# Radio.net
KiCad netlist of a schematic drawn in Altium Designer
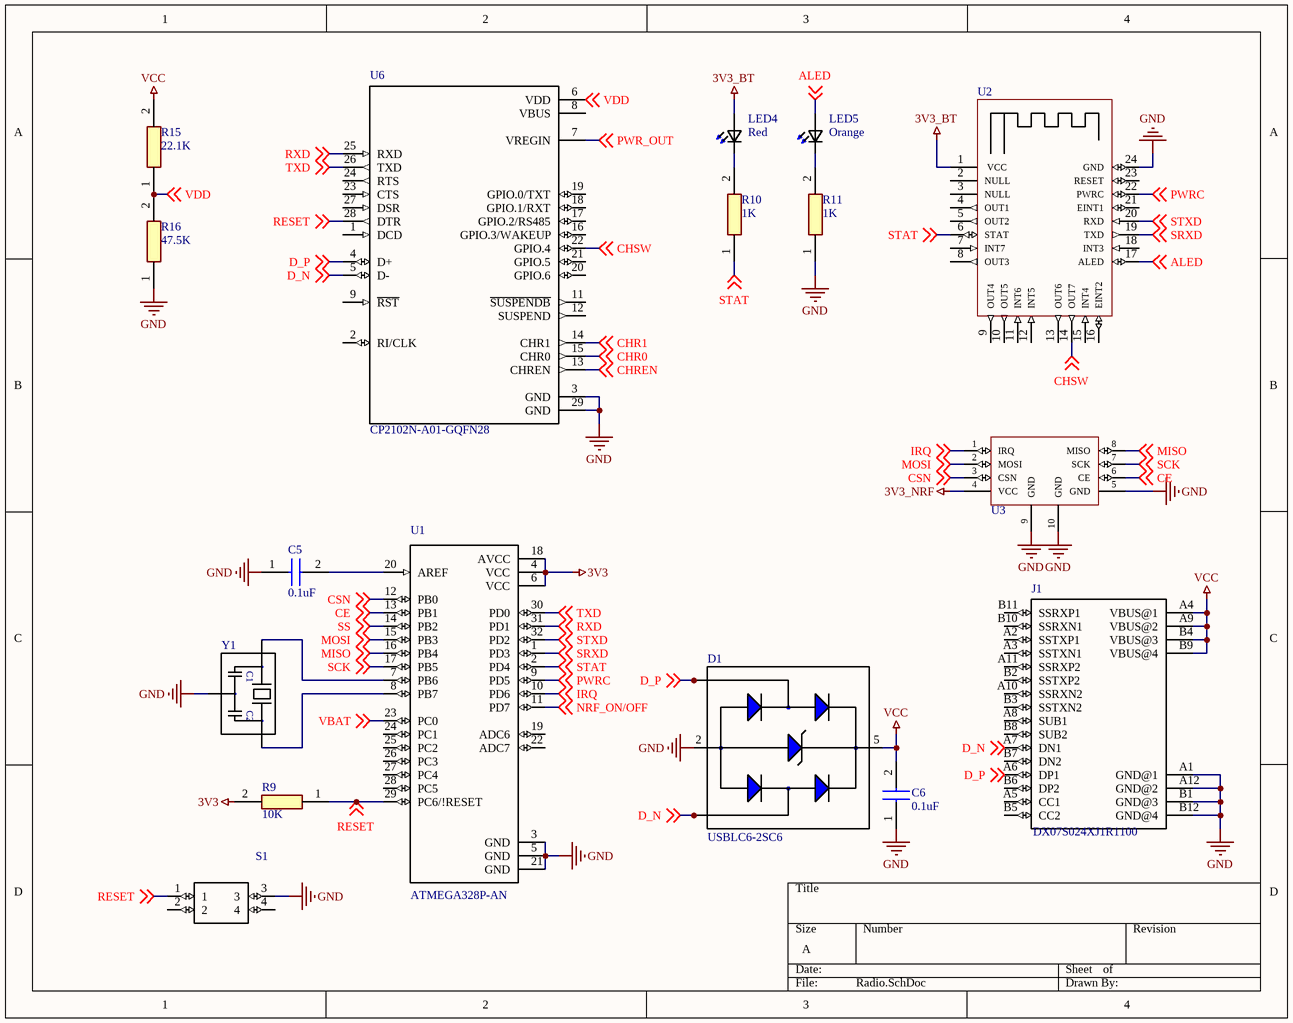
[diagram p0: Radio.SchDoc]

(export (version "E")
  (design (tool "Eeschema 10.0.6"))
  (components
    (comp (ref "C5")
      (value "0.1uF")
      (footprint "*CAPC1608X95N")
      (description "Capacitor")
      (fields (field (name "Comment") "capacitor 0603"))
      (libsource (lib "Radio Lib") (part "capacitor 0603"))
    )
    (comp (ref "C6")
      (value "0.1uF")
      (footprint "*CAPC1608X95N")
      (description "Capacitor")
      (fields (field (name "Comment") "capacitor 0603"))
      (libsource (lib "Radio Lib") (part "capacitor 0603"))
    )
    (comp (ref "D1")
      (value "USBLC6-2SC6")
      (footprint "*SOT95P280X145-6N")
      (description "USBLC6 Series 2 Line 6 V Uni / Bi-Directional ESD Protection - SOT-23-6")
      (fields (field (name "MF") "STMicroelectronics"))
      (libsource (lib "Radio Lib") (part "USBLC6-2SC6"))
    )
    (comp (ref "J1")
      (value "DX07S024XJ1R1100")
      (footprint "*JAE_DX07S024XJ1R1100_DX07S024XJ1R1100(Primary)")
      (description "Cut Tape - Usb Type c Receptacle Mid Mnt Dual r")
      (fields (field (name "MF") "JAE Electronics"))
      (libsource (lib "Radio Lib") (part "DX07S024XJ1R1100"))
    )
    (comp (ref "LED4")
      (value "Red")
      (footprint "*0603")
      (description "LED Indication - Discrete 3.4V 0603 _1608 Metric_")
      (fields (field (name "MP") "HSMR-C191") (field (name "MF") "Broadcom Limited"))
      (libsource (lib "Radio Lib") (part "HSMR-C191"))
    )
    (comp (ref "LED5")
      (value "Orange")
      (footprint "*0603")
      (description "LED Indication - Discrete 3.4V 0603 _1608 Metric_")
      (fields (field (name "MP") "HSMR-C191") (field (name "MF") "Broadcom Limited"))
      (libsource (lib "Radio Lib") (part "HSMR-C191"))
    )
    (comp (ref "R9")
      (value "10K")
      (footprint "RESC1608X55N")
      (description "Resistor")
      (fields (field (name "Comment") "resistor"))
      (libsource (lib "") (part "resistor_1"))
    )
    (comp (ref "R10")
      (value "1K")
      (footprint "RESC1608X55N")
      (description "Resistor")
      (fields (field (name "Comment") "resistor"))
      (libsource (lib "Radio Lib") (part "resistor"))
    )
    (comp (ref "R11")
      (value "1K")
      (footprint "RESC1608X55N")
      (description "Resistor")
      (fields (field (name "Comment") "resistor"))
      (libsource (lib "Radio Lib") (part "resistor"))
    )
    (comp (ref "R15")
      (value "22.1K")
      (footprint "RESC1608X55N")
      (description "Resistor")
      (fields (field (name "Comment") "resistor"))
      (libsource (lib "Radio Lib") (part "resistor"))
    )
    (comp (ref "R16")
      (value "47.5K")
      (footprint "RESC1608X55N")
      (description "Resistor")
      (fields (field (name "Comment") "resistor"))
      (libsource (lib "Radio Lib") (part "resistor"))
    )
    (comp (ref "S1")
      (value "PTS810SJK250SMTRLFS")
      (footprint "*PTS810SJG250SMTRLFS")
      (description "Tactile Switch SPST-NO Top Actuated Surface Mount")
      (fields (field (name "MP") "PTS810 SJK 250 SMTR LFS") (field (name "MF") "C&K"))
      (libsource (lib "Radio Lib") (part "PTS810SJK250SMTRLFS"))
    )
    (comp (ref "U1")
      (value "ATMEGA328P-AN")
      (footprint "*QFP80P900X900X120-32N")
      (description "AVR AVRÂ® ATmega Microcontroller IC 8-Bit 20MHz 32KB _16K x 16_ FLASH 32-TQFP _7x7_")
      (fields (field (name "MF") "Microchip"))
      (libsource (lib "Radio Lib") (part "ATMEGA328P-AN"))
    )
    (comp (ref "U2")
      (value "JDY-23")
      (footprint "*JDY-23")
      (description "Bluetooth Bluetooth v4.0 Transceiver Module 2.4GHz Integrated, Chip Surface Mount")
      (fields (field (name "MF") "Sierra Wireless"))
      (libsource (lib "Radio Lib") (part "JDY-23"))
    )
    (comp (ref "U3")
      (value "NRF24L01P+")
      (footprint "NRF24L01P+")
      (libsource (lib "Radio Lib") (part "NRF24L01P+"))
    )
    (comp (ref "U6")
      (value "CP2102N-A01-GQFN28")
      (footprint "*QFN50P500X500X80-29N")
      (description "USB Bridge, USB to UART USB 2.0 UART Interface 28-QFN _5x5_")
      (fields (field (name "MF") "Silicon Labs"))
      (libsource (lib "Radio Lib") (part "CP2102N-A01-GQFN28"))
    )
    (comp (ref "Y1")
      (value "PBRC8.00MR10X000")
      (footprint "*XTAL_PBRC8.00MR10X000")
      (description "8MHz Ceramic Resonator Built in Capacitor 15pF Â±0.1% -40Â°C ~ 85Â°C Surface Mount")
      (fields (field (name "MF") "Kyocera International"))
      (libsource (lib "Radio Lib") (part "PBRC8.00MR10X000"))
    )
  )
  (nets
    (net (code "1") (name "3V3") (class "Default")
      (node (ref "R9") (pin "2") (pinfunction "2_2") (pintype "passive"))
      (node (ref "U1") (pin "18") (pinfunction "AVCC_18") (pintype "power_in"))
      (node (ref "U1") (pin "4") (pinfunction "VCC_4") (pintype "power_in"))
      (node (ref "U1") (pin "6") (pinfunction "VCC_6") (pintype "power_in"))
    )
    (net (code "2") (name "3V3_BT") (class "Default")
      (node (ref "LED4") (pin "2") (pinfunction "A2_2") (pintype "passive"))
      (node (ref "U2") (pin "1") (pinfunction "VCC_1") (pintype "power_in"))
    )
    (net (code "3") (name "3V3_NRF") (class "Default")
      (node (ref "U3") (pin "4") (pinfunction "VCC_4") (pintype "power_in"))
    )
    (net (code "4") (name "ALED") (class "Default")
      (node (ref "LED5") (pin "2") (pinfunction "A2_2") (pintype "passive"))
      (node (ref "U2") (pin "17") (pinfunction "ALED_17") (pintype "bidirectional"))
    )
    (net (code "5") (name "CE") (class "Default")
      (node (ref "U1") (pin "13") (pinfunction "PB1_13") (pintype "bidirectional"))
      (node (ref "U3") (pin "6") (pinfunction "CE_6") (pintype "bidirectional"))
    )
    (net (code "6") (name "CHR0") (class "Default")
      (node (ref "U6") (pin "15") (pinfunction "CHR0_15") (pintype "output"))
    )
    (net (code "7") (name "CHR1") (class "Default")
      (node (ref "U6") (pin "14") (pinfunction "CHR1_14") (pintype "output"))
    )
    (net (code "8") (name "CHREN") (class "Default")
      (node (ref "U6") (pin "13") (pinfunction "CHREN_13") (pintype "output"))
    )
    (net (code "9") (name "CHSW") (class "Default")
      (node (ref "U2") (pin "14") (pinfunction "OUT7_14") (pintype "output"))
      (node (ref "U6") (pin "22") (pinfunction "GPIO.4_22") (pintype "bidirectional"))
    )
    (net (code "10") (name "CSN") (class "Default")
      (node (ref "U1") (pin "12") (pinfunction "PB0_12") (pintype "bidirectional"))
      (node (ref "U3") (pin "3") (pinfunction "CSN_3") (pintype "bidirectional"))
    )
    (net (code "11") (name "D_N") (class "Default")
      (node (ref "D1") (pin "3") (pinfunction "I/O2_3") (pintype "bidirectional"))
      (node (ref "D1") (pin "4") (pinfunction "I/O2_4") (pintype "bidirectional"))
      (node (ref "J1") (pin "A7") (pinfunction "DN1_A7") (pintype "bidirectional"))
      (node (ref "U6") (pin "5") (pinfunction "D-_5") (pintype "bidirectional"))
    )
    (net (code "12") (name "D_P") (class "Default")
      (node (ref "D1") (pin "1") (pinfunction "I/O1_1") (pintype "bidirectional"))
      (node (ref "D1") (pin "6") (pinfunction "I/O1_6") (pintype "bidirectional"))
      (node (ref "J1") (pin "A6") (pinfunction "DP1_A6") (pintype "bidirectional"))
      (node (ref "U6") (pin "4") (pinfunction "D+_4") (pintype "bidirectional"))
    )
    (net (code "13") (name "GND") (class "Default")
      (node (ref "C5") (pin "1") (pinfunction "1_1") (pintype "passive"))
      (node (ref "C6") (pin "1") (pinfunction "1_1") (pintype "passive"))
      (node (ref "D1") (pin "2") (pinfunction "GND_2") (pintype "power_in"))
      (node (ref "J1") (pin "A1") (pinfunction "GND@1_A1") (pintype "power_in"))
      (node (ref "J1") (pin "A12") (pinfunction "GND@2_A12") (pintype "power_in"))
      (node (ref "J1") (pin "B1") (pinfunction "GND@3_B1") (pintype "power_in"))
      (node (ref "J1") (pin "B12") (pinfunction "GND@4_B12") (pintype "power_in"))
      (node (ref "R11") (pin "1") (pinfunction "1_1") (pintype "passive"))
      (node (ref "R16") (pin "1") (pinfunction "1_1") (pintype "passive"))
      (node (ref "S1") (pin "3") (pinfunction "3_3") (pintype "bidirectional"))
      (node (ref "U1") (pin "21") (pinfunction "GND_21") (pintype "power_in"))
      (node (ref "U1") (pin "3") (pinfunction "GND_3") (pintype "power_in"))
      (node (ref "U1") (pin "5") (pinfunction "GND_5") (pintype "power_in"))
      (node (ref "U2") (pin "24") (pinfunction "GND_24") (pintype "bidirectional"))
      (node (ref "U3") (pin "10") (pinfunction "GND_10") (pintype "power_in"))
      (node (ref "U3") (pin "5") (pinfunction "GND_5") (pintype "power_in"))
      (node (ref "U3") (pin "9") (pinfunction "GND_9") (pintype "power_in"))
      (node (ref "U6") (pin "29") (pinfunction "GND_29") (pintype "power_in"))
      (node (ref "U6") (pin "3") (pinfunction "GND_3") (pintype "power_in"))
      (node (ref "Y1") (pin "2") (pinfunction "GND_2") (pintype "passive"))
    )
    (net (code "14") (name "IRQ") (class "Default")
      (node (ref "U1") (pin "10") (pinfunction "PD6_10") (pintype "bidirectional"))
      (node (ref "U3") (pin "1") (pinfunction "IRQ_1") (pintype "bidirectional"))
    )
    (net (code "15") (name "MISO") (class "Default")
      (node (ref "U1") (pin "16") (pinfunction "PB4_16") (pintype "bidirectional"))
      (node (ref "U3") (pin "8") (pinfunction "MISO_8") (pintype "bidirectional"))
    )
    (net (code "16") (name "MOSI") (class "Default")
      (node (ref "U1") (pin "15") (pinfunction "PB3_15") (pintype "bidirectional"))
      (node (ref "U3") (pin "2") (pinfunction "MOSI_2") (pintype "bidirectional"))
    )
    (net (code "17") (name "NRF_ON{slash}OFF") (class "Default")
      (node (ref "U1") (pin "11") (pinfunction "PD7_11") (pintype "bidirectional"))
    )
    (net (code "18") (name "Net-(LED4-K2)") (class "Default")
      (node (ref "LED4") (pin "1") (pinfunction "K2_1") (pintype "passive"))
      (node (ref "R10") (pin "2") (pinfunction "2_2") (pintype "passive"))
    )
    (net (code "19") (name "Net-(LED5-K2)") (class "Default")
      (node (ref "LED5") (pin "1") (pinfunction "K2_1") (pintype "passive"))
      (node (ref "R11") (pin "2") (pinfunction "2_2") (pintype "passive"))
    )
    (net (code "20") (name "Net-(U1-AREF)") (class "Default")
      (node (ref "C5") (pin "2") (pinfunction "2_2") (pintype "passive"))
      (node (ref "U1") (pin "20") (pinfunction "AREF_20") (pintype "input"))
    )
    (net (code "21") (name "Net-(U1-PB6)") (class "Default")
      (node (ref "U1") (pin "7") (pinfunction "PB6_7") (pintype "bidirectional"))
      (node (ref "Y1") (pin "1") (pinfunction "IN_1") (pintype "passive"))
    )
    (net (code "22") (name "Net-(U1-PB7)") (class "Default")
      (node (ref "U1") (pin "8") (pinfunction "PB7_8") (pintype "bidirectional"))
      (node (ref "Y1") (pin "3") (pinfunction "OUT_3") (pintype "passive"))
    )
    (net (code "23") (name "PWRC") (class "Default")
      (node (ref "U1") (pin "9") (pinfunction "PD5_9") (pintype "bidirectional"))
      (node (ref "U2") (pin "22") (pinfunction "PWRC_22") (pintype "bidirectional"))
    )
    (net (code "24") (name "PWR_OUT") (class "Default")
      (node (ref "U6") (pin "7") (pinfunction "VREGIN_7") (pintype "power_in"))
    )
    (net (code "25") (name "RESET") (class "Default")
      (node (ref "R9") (pin "1") (pinfunction "1_1") (pintype "passive"))
      (node (ref "S1") (pin "1") (pinfunction "1_1") (pintype "bidirectional"))
      (node (ref "U1") (pin "29") (pinfunction "PC6/!RESET_29") (pintype "bidirectional"))
      (node (ref "U6") (pin "28") (pinfunction "DTR_28") (pintype "output"))
    )
    (net (code "26") (name "RXD") (class "Default")
      (node (ref "U1") (pin "31") (pinfunction "PD1_31") (pintype "bidirectional"))
      (node (ref "U6") (pin "25") (pinfunction "RXD_25") (pintype "input"))
    )
    (net (code "27") (name "SCK") (class "Default")
      (node (ref "U1") (pin "17") (pinfunction "PB5_17") (pintype "bidirectional"))
      (node (ref "U3") (pin "7") (pinfunction "SCK_7") (pintype "bidirectional"))
    )
    (net (code "28") (name "SRXD") (class "Default")
      (node (ref "U1") (pin "1") (pinfunction "PD3_1") (pintype "bidirectional"))
      (node (ref "U2") (pin "19") (pinfunction "TXD_19") (pintype "output"))
    )
    (net (code "29") (name "SS") (class "Default")
      (node (ref "U1") (pin "14") (pinfunction "PB2_14") (pintype "bidirectional"))
    )
    (net (code "30") (name "STAT") (class "Default")
      (node (ref "R10") (pin "1") (pinfunction "1_1") (pintype "passive"))
      (node (ref "U1") (pin "2") (pinfunction "PD4_2") (pintype "bidirectional"))
      (node (ref "U2") (pin "6") (pinfunction "STAT_6") (pintype "bidirectional"))
    )
    (net (code "31") (name "STXD") (class "Default")
      (node (ref "U1") (pin "32") (pinfunction "PD2_32") (pintype "bidirectional"))
      (node (ref "U2") (pin "20") (pinfunction "RXD_20") (pintype "input"))
    )
    (net (code "32") (name "TXD") (class "Default")
      (node (ref "U1") (pin "30") (pinfunction "PD0_30") (pintype "bidirectional"))
      (node (ref "U6") (pin "26") (pinfunction "TXD_26") (pintype "output"))
    )
    (net (code "33") (name "VBAT") (class "Default")
      (node (ref "U1") (pin "23") (pinfunction "PC0_23") (pintype "bidirectional"))
    )
    (net (code "34") (name "VCC") (class "Default")
      (node (ref "C6") (pin "2") (pinfunction "2_2") (pintype "passive"))
      (node (ref "D1") (pin "5") (pinfunction "VBUS_5") (pintype "power_in"))
      (node (ref "J1") (pin "A4") (pinfunction "VBUS@1_A4") (pintype "power_in"))
      (node (ref "J1") (pin "A9") (pinfunction "VBUS@2_A9") (pintype "power_in"))
      (node (ref "J1") (pin "B4") (pinfunction "VBUS@3_B4") (pintype "power_in"))
      (node (ref "J1") (pin "B9") (pinfunction "VBUS@4_B9") (pintype "power_in"))
      (node (ref "R15") (pin "2") (pinfunction "2_2") (pintype "passive"))
    )
    (net (code "35") (name "VDD") (class "Default")
      (node (ref "R15") (pin "1") (pinfunction "1_1") (pintype "passive"))
      (node (ref "R16") (pin "2") (pinfunction "2_2") (pintype "passive"))
      (node (ref "U6") (pin "6") (pinfunction "VDD_6") (pintype "power_in"))
    )
    (net (code "36") (name "unconnected-(J1-CC1-PadA5)") (class "Default")
      (node (ref "J1") (pin "A5") (pinfunction "CC1_A5") (pintype "bidirectional"))
    )
    (net (code "37") (name "unconnected-(J1-CC2-PadB5)") (class "Default")
      (node (ref "J1") (pin "B5") (pinfunction "CC2_B5") (pintype "bidirectional"))
    )
    (net (code "38") (name "unconnected-(J1-DN2-PadB7)") (class "Default")
      (node (ref "J1") (pin "B7") (pinfunction "DN2_B7") (pintype "bidirectional"))
    )
    (net (code "39") (name "unconnected-(J1-DP2-PadB6)") (class "Default")
      (node (ref "J1") (pin "B6") (pinfunction "DP2_B6") (pintype "bidirectional"))
    )
    (net (code "40") (name "unconnected-(J1-SSRXN1-PadB10)") (class "Default")
      (node (ref "J1") (pin "B10") (pinfunction "SSRXN1_B10") (pintype "bidirectional"))
    )
    (net (code "41") (name "unconnected-(J1-SSRXN2-PadA10)") (class "Default")
      (node (ref "J1") (pin "A10") (pinfunction "SSRXN2_A10") (pintype "bidirectional"))
    )
    (net (code "42") (name "unconnected-(J1-SSRXP1-PadB11)") (class "Default")
      (node (ref "J1") (pin "B11") (pinfunction "SSRXP1_B11") (pintype "bidirectional"))
    )
    (net (code "43") (name "unconnected-(J1-SSRXP2-PadA11)") (class "Default")
      (node (ref "J1") (pin "A11") (pinfunction "SSRXP2_A11") (pintype "bidirectional"))
    )
    (net (code "44") (name "unconnected-(J1-SSTXN1-PadA3)") (class "Default")
      (node (ref "J1") (pin "A3") (pinfunction "SSTXN1_A3") (pintype "bidirectional"))
    )
    (net (code "45") (name "unconnected-(J1-SSTXN2-PadB3)") (class "Default")
      (node (ref "J1") (pin "B3") (pinfunction "SSTXN2_B3") (pintype "bidirectional"))
    )
    (net (code "46") (name "unconnected-(J1-SSTXP1-PadA2)") (class "Default")
      (node (ref "J1") (pin "A2") (pinfunction "SSTXP1_A2") (pintype "bidirectional"))
    )
    (net (code "47") (name "unconnected-(J1-SSTXP2-PadB2)") (class "Default")
      (node (ref "J1") (pin "B2") (pinfunction "SSTXP2_B2") (pintype "bidirectional"))
    )
    (net (code "48") (name "unconnected-(J1-SUB1-PadA8)") (class "Default")
      (node (ref "J1") (pin "A8") (pinfunction "SUB1_A8") (pintype "bidirectional"))
    )
    (net (code "49") (name "unconnected-(J1-SUB2-PadB8)") (class "Default")
      (node (ref "J1") (pin "B8") (pinfunction "SUB2_B8") (pintype "bidirectional"))
    )
    (net (code "50") (name "unconnected-(S1-Pad2)") (class "Default")
      (node (ref "S1") (pin "2") (pinfunction "2_2") (pintype "bidirectional"))
    )
    (net (code "51") (name "unconnected-(S1-Pad4)") (class "Default")
      (node (ref "S1") (pin "4") (pinfunction "4_4") (pintype "bidirectional"))
    )
    (net (code "52") (name "unconnected-(U1-ADC6-Pad19)") (class "Default")
      (node (ref "U1") (pin "19") (pinfunction "ADC6_19") (pintype "bidirectional"))
    )
    (net (code "53") (name "unconnected-(U1-ADC7-Pad22)") (class "Default")
      (node (ref "U1") (pin "22") (pinfunction "ADC7_22") (pintype "bidirectional"))
    )
    (net (code "54") (name "unconnected-(U1-PC1-Pad24)") (class "Default")
      (node (ref "U1") (pin "24") (pinfunction "PC1_24") (pintype "bidirectional"))
    )
    (net (code "55") (name "unconnected-(U1-PC2-Pad25)") (class "Default")
      (node (ref "U1") (pin "25") (pinfunction "PC2_25") (pintype "bidirectional"))
    )
    (net (code "56") (name "unconnected-(U1-PC3-Pad26)") (class "Default")
      (node (ref "U1") (pin "26") (pinfunction "PC3_26") (pintype "bidirectional"))
    )
    (net (code "57") (name "unconnected-(U1-PC4-Pad27)") (class "Default")
      (node (ref "U1") (pin "27") (pinfunction "PC4_27") (pintype "bidirectional"))
    )
    (net (code "58") (name "unconnected-(U1-PC5-Pad28)") (class "Default")
      (node (ref "U1") (pin "28") (pinfunction "PC5_28") (pintype "bidirectional"))
    )
    (net (code "59") (name "unconnected-(U2-EINT1-Pad21)") (class "Default")
      (node (ref "U2") (pin "21") (pinfunction "EINT1_21") (pintype "bidirectional"))
    )
    (net (code "60") (name "unconnected-(U2-EINT2-Pad16)") (class "Default")
      (node (ref "U2") (pin "16") (pinfunction "EINT2_16") (pintype "bidirectional"))
    )
    (net (code "61") (name "unconnected-(U2-INT3-Pad18)") (class "Default")
      (node (ref "U2") (pin "18") (pinfunction "INT3_18") (pintype "input"))
    )
    (net (code "62") (name "unconnected-(U2-INT4-Pad15)") (class "Default")
      (node (ref "U2") (pin "15") (pinfunction "INT4_15") (pintype "input"))
    )
    (net (code "63") (name "unconnected-(U2-INT5-Pad12)") (class "Default")
      (node (ref "U2") (pin "12") (pinfunction "INT5_12") (pintype "input"))
    )
    (net (code "64") (name "unconnected-(U2-INT6-Pad11)") (class "Default")
      (node (ref "U2") (pin "11") (pinfunction "INT6_11") (pintype "input"))
    )
    (net (code "65") (name "unconnected-(U2-INT7-Pad7)") (class "Default")
      (node (ref "U2") (pin "7") (pinfunction "INT7_7") (pintype "input"))
    )
    (net (code "66") (name "unconnected-(U2-NULL-Pad2)") (class "Default")
      (node (ref "U2") (pin "2") (pinfunction "NULL_2") (pintype "power_in"))
    )
    (net (code "67") (name "unconnected-(U2-NULL-Pad3)") (class "Default")
      (node (ref "U2") (pin "3") (pinfunction "NULL_3") (pintype "power_in"))
    )
    (net (code "68") (name "unconnected-(U2-OUT1-Pad4)") (class "Default")
      (node (ref "U2") (pin "4") (pinfunction "OUT1_4") (pintype "output"))
    )
    (net (code "69") (name "unconnected-(U2-OUT2-Pad5)") (class "Default")
      (node (ref "U2") (pin "5") (pinfunction "OUT2_5") (pintype "output"))
    )
    (net (code "70") (name "unconnected-(U2-OUT3-Pad8)") (class "Default")
      (node (ref "U2") (pin "8") (pinfunction "OUT3_8") (pintype "output"))
    )
    (net (code "71") (name "unconnected-(U2-OUT4-Pad9)") (class "Default")
      (node (ref "U2") (pin "9") (pinfunction "OUT4_9") (pintype "output"))
    )
    (net (code "72") (name "unconnected-(U2-OUT5-Pad10)") (class "Default")
      (node (ref "U2") (pin "10") (pinfunction "OUT5_10") (pintype "output"))
    )
    (net (code "73") (name "unconnected-(U2-OUT6-Pad13)") (class "Default")
      (node (ref "U2") (pin "13") (pinfunction "OUT6_13") (pintype "output"))
    )
    (net (code "74") (name "unconnected-(U2-RESET-Pad23)") (class "Default")
      (node (ref "U2") (pin "23") (pinfunction "RESET_23") (pintype "bidirectional"))
    )
    (net (code "75") (name "unconnected-(U6-CTS-Pad23)") (class "Default")
      (node (ref "U6") (pin "23") (pinfunction "CTS_23") (pintype "input"))
    )
    (net (code "76") (name "unconnected-(U6-DCD-Pad1)") (class "Default")
      (node (ref "U6") (pin "1") (pinfunction "DCD_1") (pintype "input"))
    )
    (net (code "77") (name "unconnected-(U6-DSR-Pad27)") (class "Default")
      (node (ref "U6") (pin "27") (pinfunction "DSR_27") (pintype "input"))
    )
    (net (code "78") (name "unconnected-(U6-GPIO.0{slash}TXT-Pad19)") (class "Default")
      (node (ref "U6") (pin "19") (pinfunction "GPIO.0/TXT_19") (pintype "bidirectional"))
    )
    (net (code "79") (name "unconnected-(U6-GPIO.1{slash}RXT-Pad18)") (class "Default")
      (node (ref "U6") (pin "18") (pinfunction "GPIO.1/RXT_18") (pintype "bidirectional"))
    )
    (net (code "80") (name "unconnected-(U6-GPIO.2{slash}RS485-Pad17)") (class "Default")
      (node (ref "U6") (pin "17") (pinfunction "GPIO.2/RS485_17") (pintype "bidirectional"))
    )
    (net (code "81") (name "unconnected-(U6-GPIO.3{slash}WAKEUP-Pad16)") (class "Default")
      (node (ref "U6") (pin "16") (pinfunction "GPIO.3/WAKEUP_16") (pintype "bidirectional"))
    )
    (net (code "82") (name "unconnected-(U6-GPIO.5-Pad21)") (class "Default")
      (node (ref "U6") (pin "21") (pinfunction "GPIO.5_21") (pintype "bidirectional"))
    )
    (net (code "83") (name "unconnected-(U6-GPIO.6-Pad20)") (class "Default")
      (node (ref "U6") (pin "20") (pinfunction "GPIO.6_20") (pintype "bidirectional"))
    )
    (net (code "84") (name "unconnected-(U6-RI{slash}CLK-Pad2)") (class "Default")
      (node (ref "U6") (pin "2") (pinfunction "RI/CLK_2") (pintype "bidirectional"))
    )
    (net (code "85") (name "unconnected-(U6-RTS-Pad24)") (class "Default")
      (node (ref "U6") (pin "24") (pinfunction "RTS_24") (pintype "output"))
    )
    (net (code "86") (name "unconnected-(U6-SUSPEND-Pad12)") (class "Default")
      (node (ref "U6") (pin "12") (pinfunction "SUSPEND_12") (pintype "output"))
    )
    (net (code "87") (name "unconnected-(U6-VBUS-Pad8)") (class "Default")
      (node (ref "U6") (pin "8") (pinfunction "VBUS_8") (pintype "power_in"))
    )
    (net (code "88") (name "unconnected-(U6-~{RST}-Pad9)") (class "Default")
      (node (ref "U6") (pin "9") (pinfunction "~{RST}_9") (pintype "input"))
    )
    (net (code "89") (name "unconnected-(U6-~{SUSPENDB}-Pad11)") (class "Default")
      (node (ref "U6") (pin "11") (pinfunction "~{SUSPENDB}_11") (pintype "output"))
    )
  )
)
